# Controller.net
KiCad netlist of a schematic drawn in EAGLE
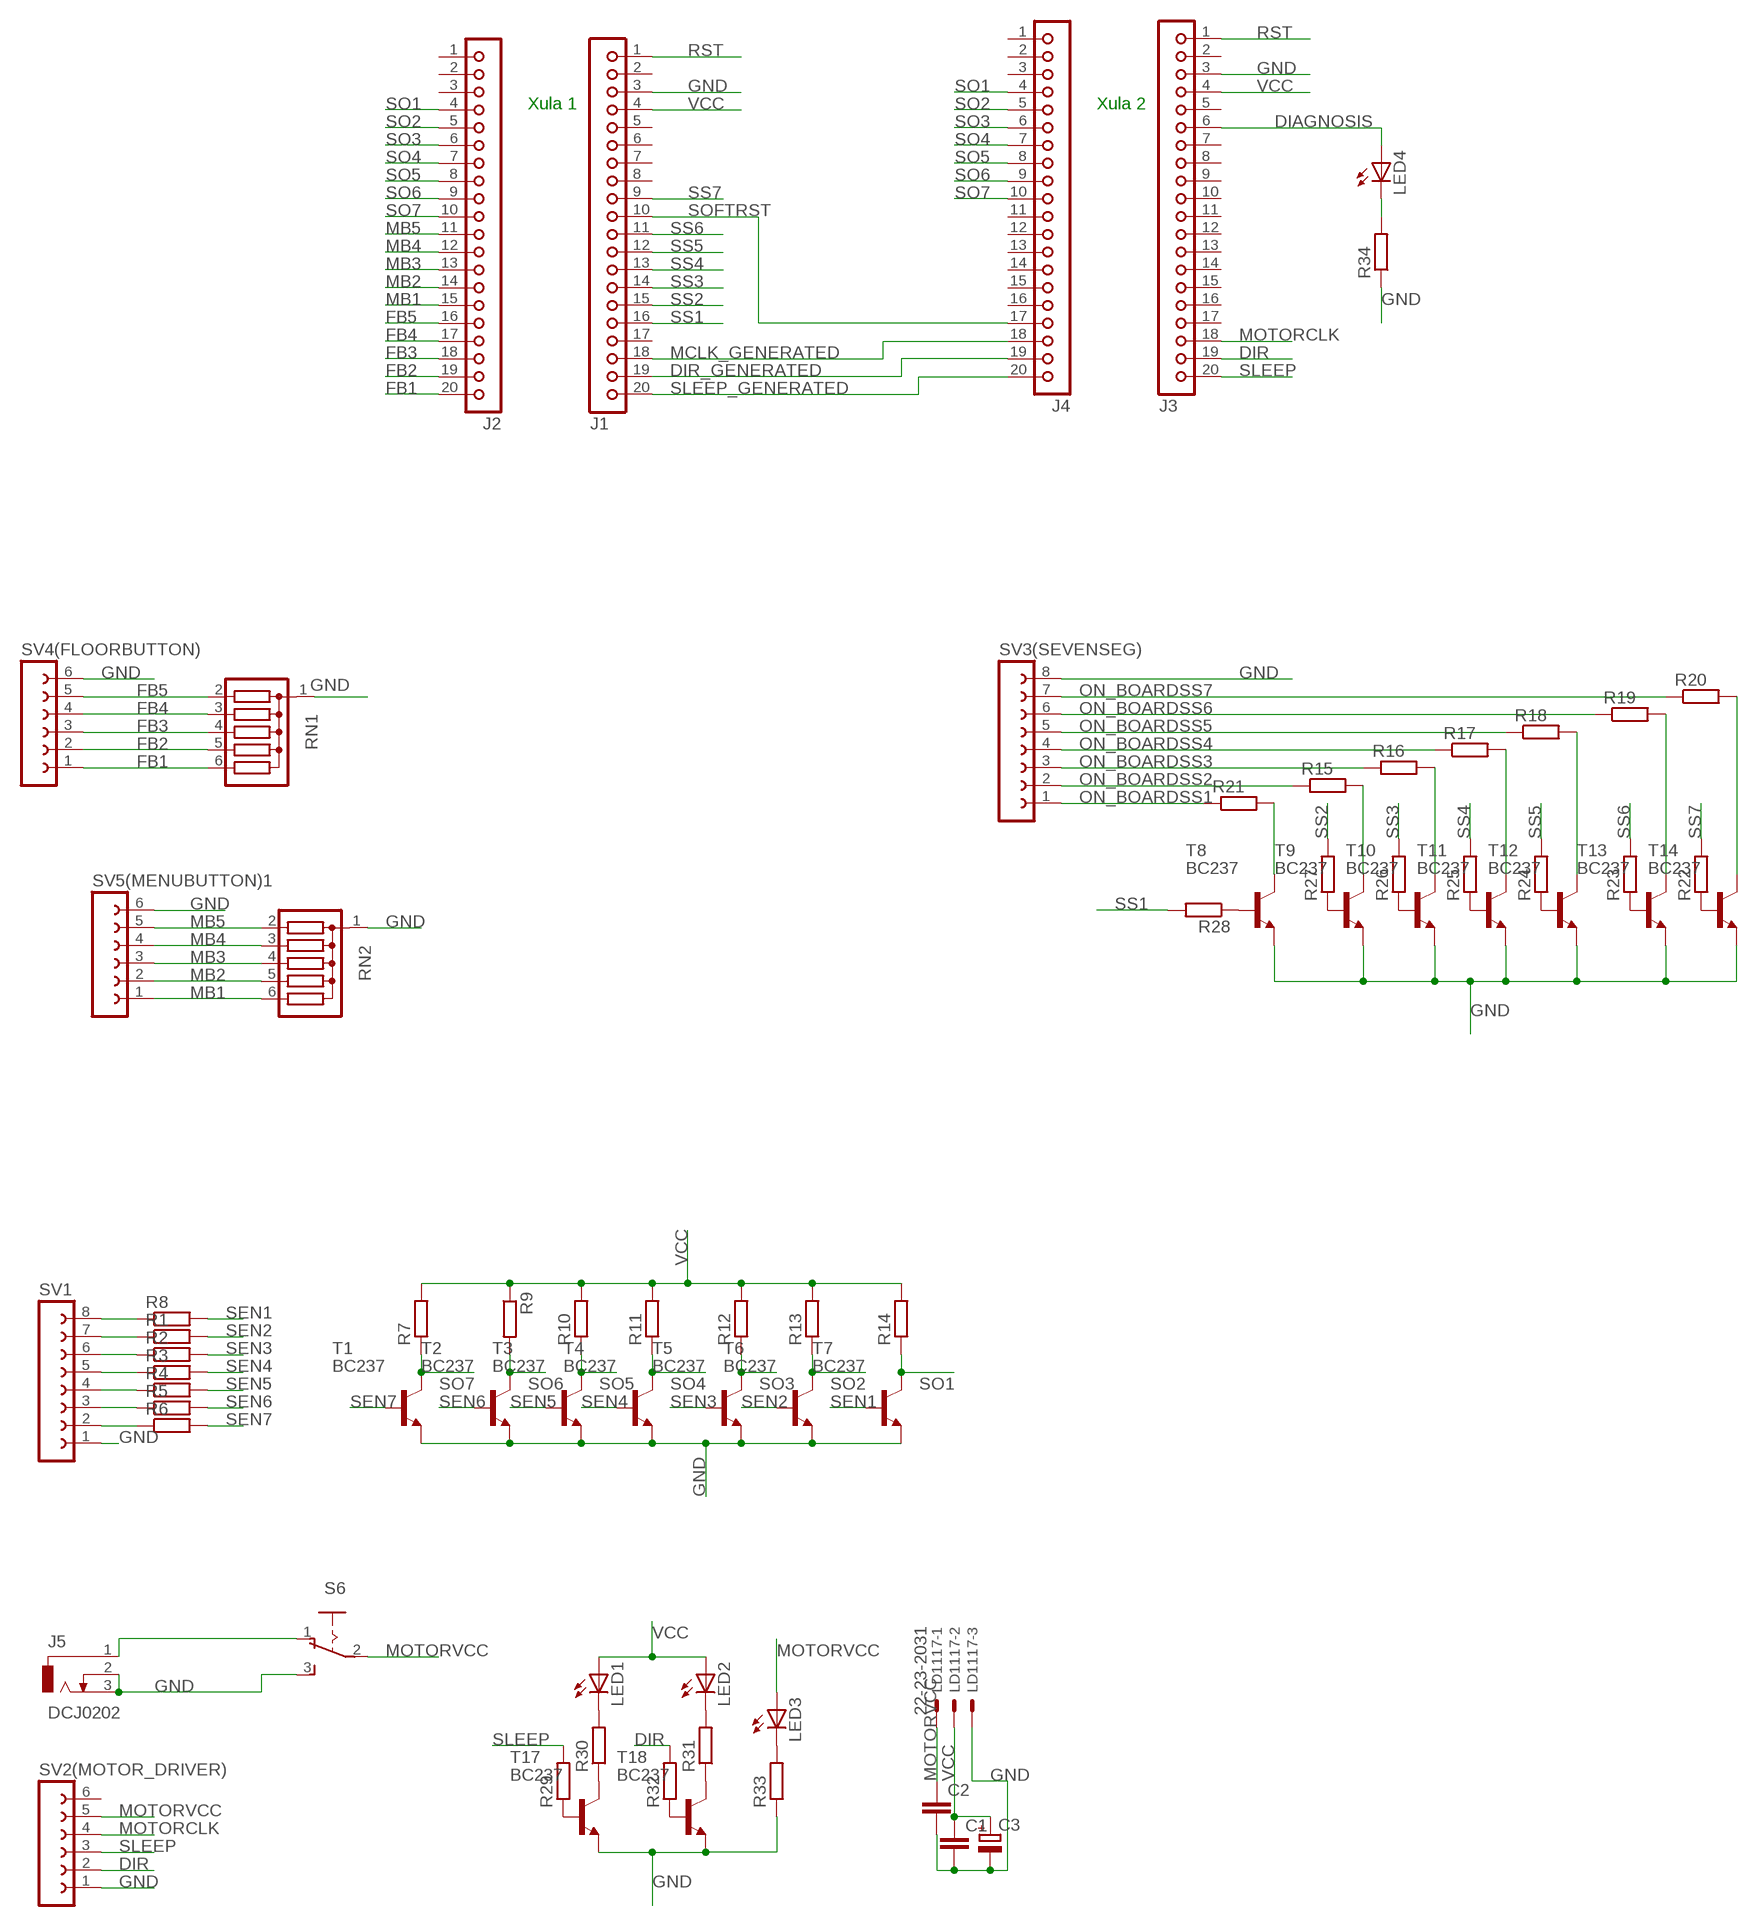
[diagram p0: schematic, sheet 1]

(export (version "E")
  (design (tool "Eeschema 10.0.6"))
  (components
    (comp (ref "C1")
      (value "C-EU025-025X050")
      (footprint "eagle-import:C025-025X050")
      (libsource (lib "eagle-import") (part "C-EU025-025X050"))
    )
    (comp (ref "C2")
      (value "C-EU025-025X050")
      (footprint "eagle-import:C025-025X050")
      (libsource (lib "eagle-import") (part "C-EU025-025X050"))
    )
    (comp (ref "C3")
      (value "CPOL-EUE3.5-8")
      (footprint "eagle-import:E3,5-8")
      (libsource (lib "eagle-import") (part "CPOL-EUE3.5-8"))
    )
    (comp (ref "J1")
      (value "JBK20")
      (footprint "eagle-import:JBK20")
      (libsource (lib "eagle-import") (part "JBK20"))
    )
    (comp (ref "J2")
      (value "JBK20")
      (footprint "eagle-import:JBK20")
      (libsource (lib "eagle-import") (part "JBK20"))
    )
    (comp (ref "J3")
      (value "JBK20")
      (footprint "eagle-import:JBK20")
      (libsource (lib "eagle-import") (part "JBK20"))
    )
    (comp (ref "J4")
      (value "JBK20")
      (footprint "eagle-import:JBK20")
      (libsource (lib "eagle-import") (part "JBK20"))
    )
    (comp (ref "J5")
      (value "DCJ0202")
      (footprint "eagle-import:DCJ0202")
      (libsource (lib "eagle-import") (part "DCJ0202"))
    )
    (comp (ref "LD1117")
      (value "22-23-2031")
      (footprint "eagle-import:22-23-2031")
      (fields (field (name "MF") "MOLEX"))
      (libsource (lib "eagle-import") (part "22-23-2031"))
    )
    (comp (ref "LED1")
      (value "LED3MM")
      (footprint "eagle-import:LED3MM")
      (libsource (lib "eagle-import") (part "LED3MM"))
    )
    (comp (ref "LED2")
      (value "LED3MM")
      (footprint "eagle-import:LED3MM")
      (libsource (lib "eagle-import") (part "LED3MM"))
    )
    (comp (ref "LED3")
      (value "LED3MM")
      (footprint "eagle-import:LED3MM")
      (libsource (lib "eagle-import") (part "LED3MM"))
    )
    (comp (ref "LED4")
      (value "LED3MM")
      (footprint "eagle-import:LED3MM")
      (libsource (lib "eagle-import") (part "LED3MM"))
    )
    (comp (ref "R1")
      (value "R-EU_0204/5")
      (footprint "eagle-import:0204_5")
      (libsource (lib "eagle-import") (part "R-EU_0204/5"))
    )
    (comp (ref "R2")
      (value "R-EU_0204/5")
      (footprint "eagle-import:0204_5")
      (libsource (lib "eagle-import") (part "R-EU_0204/5"))
    )
    (comp (ref "R3")
      (value "R-EU_0204/5")
      (footprint "eagle-import:0204_5")
      (libsource (lib "eagle-import") (part "R-EU_0204/5"))
    )
    (comp (ref "R4")
      (value "R-EU_0204/5")
      (footprint "eagle-import:0204_5")
      (libsource (lib "eagle-import") (part "R-EU_0204/5"))
    )
    (comp (ref "R5")
      (value "R-EU_0204/5")
      (footprint "eagle-import:0204_5")
      (libsource (lib "eagle-import") (part "R-EU_0204/5"))
    )
    (comp (ref "R6")
      (value "R-EU_0204/5")
      (footprint "eagle-import:0204_5")
      (libsource (lib "eagle-import") (part "R-EU_0204/5"))
    )
    (comp (ref "R7")
      (value "R-EU_0204/5")
      (footprint "eagle-import:0204_5")
      (libsource (lib "eagle-import") (part "R-EU_0204/5"))
    )
    (comp (ref "R8")
      (value "R-EU_0204/5")
      (footprint "eagle-import:0204_5")
      (libsource (lib "eagle-import") (part "R-EU_0204/5"))
    )
    (comp (ref "R9")
      (value "R-EU_0204/5")
      (footprint "eagle-import:0204_5")
      (libsource (lib "eagle-import") (part "R-EU_0204/5"))
    )
    (comp (ref "R10")
      (value "R-EU_0204/5")
      (footprint "eagle-import:0204_5")
      (libsource (lib "eagle-import") (part "R-EU_0204/5"))
    )
    (comp (ref "R11")
      (value "R-EU_0204/5")
      (footprint "eagle-import:0204_5")
      (libsource (lib "eagle-import") (part "R-EU_0204/5"))
    )
    (comp (ref "R12")
      (value "R-EU_0204/5")
      (footprint "eagle-import:0204_5")
      (libsource (lib "eagle-import") (part "R-EU_0204/5"))
    )
    (comp (ref "R13")
      (value "R-EU_0204/5")
      (footprint "eagle-import:0204_5")
      (libsource (lib "eagle-import") (part "R-EU_0204/5"))
    )
    (comp (ref "R14")
      (value "R-EU_0204/5")
      (footprint "eagle-import:0204_5")
      (libsource (lib "eagle-import") (part "R-EU_0204/5"))
    )
    (comp (ref "R15")
      (value "R-EU_0204/5")
      (footprint "eagle-import:0204_5")
      (libsource (lib "eagle-import") (part "R-EU_0204/5"))
    )
    (comp (ref "R16")
      (value "R-EU_0204/5")
      (footprint "eagle-import:0204_5")
      (libsource (lib "eagle-import") (part "R-EU_0204/5"))
    )
    (comp (ref "R17")
      (value "R-EU_0204/5")
      (footprint "eagle-import:0204_5")
      (libsource (lib "eagle-import") (part "R-EU_0204/5"))
    )
    (comp (ref "R18")
      (value "R-EU_0204/5")
      (footprint "eagle-import:0204_5")
      (libsource (lib "eagle-import") (part "R-EU_0204/5"))
    )
    (comp (ref "R19")
      (value "R-EU_0204/5")
      (footprint "eagle-import:0204_5")
      (libsource (lib "eagle-import") (part "R-EU_0204/5"))
    )
    (comp (ref "R20")
      (value "R-EU_0204/5")
      (footprint "eagle-import:0204_5")
      (libsource (lib "eagle-import") (part "R-EU_0204/5"))
    )
    (comp (ref "R21")
      (value "R-EU_0204/5")
      (footprint "eagle-import:0204_5")
      (libsource (lib "eagle-import") (part "R-EU_0204/5"))
    )
    (comp (ref "R22")
      (value "R-EU_0204/5")
      (footprint "eagle-import:0204_5")
      (libsource (lib "eagle-import") (part "R-EU_0204/5"))
    )
    (comp (ref "R23")
      (value "R-EU_0204/5")
      (footprint "eagle-import:0204_5")
      (libsource (lib "eagle-import") (part "R-EU_0204/5"))
    )
    (comp (ref "R24")
      (value "R-EU_0204/5")
      (footprint "eagle-import:0204_5")
      (libsource (lib "eagle-import") (part "R-EU_0204/5"))
    )
    (comp (ref "R25")
      (value "R-EU_0204/5")
      (footprint "eagle-import:0204_5")
      (libsource (lib "eagle-import") (part "R-EU_0204/5"))
    )
    (comp (ref "R26")
      (value "R-EU_0204/5")
      (footprint "eagle-import:0204_5")
      (libsource (lib "eagle-import") (part "R-EU_0204/5"))
    )
    (comp (ref "R27")
      (value "R-EU_0204/5")
      (footprint "eagle-import:0204_5")
      (libsource (lib "eagle-import") (part "R-EU_0204/5"))
    )
    (comp (ref "R28")
      (value "R-EU_0204/5")
      (footprint "eagle-import:0204_5")
      (libsource (lib "eagle-import") (part "R-EU_0204/5"))
    )
    (comp (ref "R29")
      (value "R-EU_0204/5")
      (footprint "eagle-import:0204_5")
      (libsource (lib "eagle-import") (part "R-EU_0204/5"))
    )
    (comp (ref "R30")
      (value "R-EU_0204/5")
      (footprint "eagle-import:0204_5")
      (libsource (lib "eagle-import") (part "R-EU_0204/5"))
    )
    (comp (ref "R31")
      (value "R-EU_0204/5")
      (footprint "eagle-import:0204_5")
      (libsource (lib "eagle-import") (part "R-EU_0204/5"))
    )
    (comp (ref "R32")
      (value "R-EU_0204/5")
      (footprint "eagle-import:0204_5")
      (libsource (lib "eagle-import") (part "R-EU_0204/5"))
    )
    (comp (ref "R33")
      (value "R-EU_0204/5")
      (footprint "eagle-import:0204_5")
      (libsource (lib "eagle-import") (part "R-EU_0204/5"))
    )
    (comp (ref "R34")
      (value "R-EU_0204/5")
      (footprint "eagle-import:0204_5")
      (libsource (lib "eagle-import") (part "R-EU_0204/5"))
    )
    (comp (ref "RN1")
      (value "G05R")
      (footprint "eagle-import:SIL6")
      (libsource (lib "eagle-import") (part "G05R"))
    )
    (comp (ref "RN2")
      (value "G05R")
      (footprint "eagle-import:SIL6")
      (libsource (lib "eagle-import") (part "G05R"))
    )
    (comp (ref "S6")
      (value "255SB")
      (footprint "eagle-import:255SB")
      (libsource (lib "eagle-import") (part "255SB"))
    )
    (comp (ref "SV1")
      (value "FE08-1")
      (footprint "eagle-import:FE08")
      (libsource (lib "eagle-import") (part "FE08-1"))
    )
    (comp (ref "SV2(MOTOR_DRIVER)")
      (value "FE06-1")
      (footprint "eagle-import:FE06")
      (libsource (lib "eagle-import") (part "FE06-1"))
    )
    (comp (ref "SV3(SEVENSEG)")
      (value "FE08W")
      (footprint "eagle-import:FE08W")
      (libsource (lib "eagle-import") (part "FE08W"))
    )
    (comp (ref "SV4(FLOORBUTTON)")
      (value "FE06-1")
      (footprint "eagle-import:FE06")
      (libsource (lib "eagle-import") (part "FE06-1"))
    )
    (comp (ref "SV5(MENUBUTTON)1")
      (value "FE06-1")
      (footprint "eagle-import:FE06")
      (libsource (lib "eagle-import") (part "FE06-1"))
    )
    (comp (ref "T1")
      (value "BC237")
      (footprint "eagle-import:TO92")
      (libsource (lib "eagle-import") (part "BC237"))
    )
    (comp (ref "T2")
      (value "BC237")
      (footprint "eagle-import:TO92")
      (libsource (lib "eagle-import") (part "BC237"))
    )
    (comp (ref "T3")
      (value "BC237")
      (footprint "eagle-import:TO92")
      (libsource (lib "eagle-import") (part "BC237"))
    )
    (comp (ref "T4")
      (value "BC237")
      (footprint "eagle-import:TO92")
      (libsource (lib "eagle-import") (part "BC237"))
    )
    (comp (ref "T5")
      (value "BC237")
      (footprint "eagle-import:TO92")
      (libsource (lib "eagle-import") (part "BC237"))
    )
    (comp (ref "T6")
      (value "BC237")
      (footprint "eagle-import:TO92")
      (libsource (lib "eagle-import") (part "BC237"))
    )
    (comp (ref "T7")
      (value "BC237")
      (footprint "eagle-import:TO92")
      (libsource (lib "eagle-import") (part "BC237"))
    )
    (comp (ref "T8")
      (value "BC237")
      (footprint "eagle-import:TO92")
      (libsource (lib "eagle-import") (part "BC237"))
    )
    (comp (ref "T9")
      (value "BC237")
      (footprint "eagle-import:TO92")
      (libsource (lib "eagle-import") (part "BC237"))
    )
    (comp (ref "T10")
      (value "BC237")
      (footprint "eagle-import:TO92")
      (libsource (lib "eagle-import") (part "BC237"))
    )
    (comp (ref "T11")
      (value "BC237")
      (footprint "eagle-import:TO92")
      (libsource (lib "eagle-import") (part "BC237"))
    )
    (comp (ref "T12")
      (value "BC237")
      (footprint "eagle-import:TO92")
      (libsource (lib "eagle-import") (part "BC237"))
    )
    (comp (ref "T13")
      (value "BC237")
      (footprint "eagle-import:TO92")
      (libsource (lib "eagle-import") (part "BC237"))
    )
    (comp (ref "T14")
      (value "BC237")
      (footprint "eagle-import:TO92")
      (libsource (lib "eagle-import") (part "BC237"))
    )
    (comp (ref "T17")
      (value "BC237")
      (footprint "eagle-import:TO92")
      (libsource (lib "eagle-import") (part "BC237"))
    )
    (comp (ref "T18")
      (value "BC237")
      (footprint "eagle-import:TO92")
      (libsource (lib "eagle-import") (part "BC237"))
    )
  )
  (nets
    (net (code "1") (name "/DIAGNOSIS") (class "Default")
      (node (ref "J3") (pin "6") (pinfunction "6_6") (pintype "passive"))
      (node (ref "LED4") (pin "A") (pinfunction "A_A") (pintype "passive"))
    )
    (net (code "2") (name "/DIR") (class "Default")
      (node (ref "J3") (pin "19") (pinfunction "19_19") (pintype "passive"))
      (node (ref "R32") (pin "2") (pinfunction "2_2") (pintype "passive"))
      (node (ref "SV2(MOTOR_DRIVER)") (pin "2") (pinfunction "2_2") (pintype "passive"))
    )
    (net (code "3") (name "/DIR_GENERATED") (class "Default")
      (node (ref "J1") (pin "19") (pinfunction "19_19") (pintype "passive"))
      (node (ref "J4") (pin "19") (pinfunction "19_19") (pintype "passive"))
    )
    (net (code "4") (name "/FB1") (class "Default")
      (node (ref "J2") (pin "20") (pinfunction "20_20") (pintype "passive"))
      (node (ref "RN1") (pin "6") (pinfunction "6_6") (pintype "passive"))
      (node (ref "SV4(FLOORBUTTON)") (pin "1") (pinfunction "1_1") (pintype "passive"))
    )
    (net (code "5") (name "/FB2") (class "Default")
      (node (ref "J2") (pin "19") (pinfunction "19_19") (pintype "passive"))
      (node (ref "RN1") (pin "5") (pinfunction "5_5") (pintype "passive"))
      (node (ref "SV4(FLOORBUTTON)") (pin "2") (pinfunction "2_2") (pintype "passive"))
    )
    (net (code "6") (name "/FB3") (class "Default")
      (node (ref "J2") (pin "18") (pinfunction "18_18") (pintype "passive"))
      (node (ref "RN1") (pin "4") (pinfunction "4_4") (pintype "passive"))
      (node (ref "SV4(FLOORBUTTON)") (pin "3") (pinfunction "3_3") (pintype "passive"))
    )
    (net (code "7") (name "/FB4") (class "Default")
      (node (ref "J2") (pin "17") (pinfunction "17_17") (pintype "passive"))
      (node (ref "RN1") (pin "3") (pinfunction "3_3") (pintype "passive"))
      (node (ref "SV4(FLOORBUTTON)") (pin "4") (pinfunction "4_4") (pintype "passive"))
    )
    (net (code "8") (name "/FB5") (class "Default")
      (node (ref "J2") (pin "16") (pinfunction "16_16") (pintype "passive"))
      (node (ref "RN1") (pin "2") (pinfunction "2_2") (pintype "passive"))
      (node (ref "SV4(FLOORBUTTON)") (pin "5") (pinfunction "5_5") (pintype "passive"))
    )
    (net (code "9") (name "/GND") (class "Default")
      (node (ref "C1") (pin "2") (pinfunction "2_2") (pintype "passive"))
      (node (ref "C2") (pin "2") (pinfunction "2_2") (pintype "passive"))
      (node (ref "C3") (pin "-") (pinfunction "-_-") (pintype "passive"))
      (node (ref "J1") (pin "3") (pinfunction "3_3") (pintype "passive"))
      (node (ref "J3") (pin "3") (pinfunction "3_3") (pintype "passive"))
      (node (ref "J5") (pin "2") (pinfunction "2_2") (pintype "passive"))
      (node (ref "J5") (pin "3") (pinfunction "3_3") (pintype "passive"))
      (node (ref "LD1117") (pin "3") (pinfunction "S_3") (pintype "passive"))
      (node (ref "R33") (pin "1") (pinfunction "1_1") (pintype "passive"))
      (node (ref "R34") (pin "1") (pinfunction "1_1") (pintype "passive"))
      (node (ref "RN1") (pin "1") (pinfunction "1_1") (pintype "passive"))
      (node (ref "RN2") (pin "1") (pinfunction "1_1") (pintype "passive"))
      (node (ref "S6") (pin "3") (pinfunction "S_3") (pintype "passive"))
      (node (ref "SV1") (pin "1") (pinfunction "1_1") (pintype "passive"))
      (node (ref "SV2(MOTOR_DRIVER)") (pin "1") (pinfunction "1_1") (pintype "passive"))
      (node (ref "SV3(SEVENSEG)") (pin "8") (pinfunction "8_8") (pintype "passive"))
      (node (ref "SV4(FLOORBUTTON)") (pin "6") (pinfunction "6_6") (pintype "passive"))
      (node (ref "SV5(MENUBUTTON)1") (pin "6") (pinfunction "6_6") (pintype "passive"))
      (node (ref "T1") (pin "1") (pinfunction "E_1") (pintype "passive"))
      (node (ref "T10") (pin "1") (pinfunction "E_1") (pintype "passive"))
      (node (ref "T11") (pin "1") (pinfunction "E_1") (pintype "passive"))
      (node (ref "T12") (pin "1") (pinfunction "E_1") (pintype "passive"))
      (node (ref "T13") (pin "1") (pinfunction "E_1") (pintype "passive"))
      (node (ref "T14") (pin "1") (pinfunction "E_1") (pintype "passive"))
      (node (ref "T17") (pin "1") (pinfunction "E_1") (pintype "passive"))
      (node (ref "T18") (pin "1") (pinfunction "E_1") (pintype "passive"))
      (node (ref "T2") (pin "1") (pinfunction "E_1") (pintype "passive"))
      (node (ref "T3") (pin "1") (pinfunction "E_1") (pintype "passive"))
      (node (ref "T4") (pin "1") (pinfunction "E_1") (pintype "passive"))
      (node (ref "T5") (pin "1") (pinfunction "E_1") (pintype "passive"))
      (node (ref "T6") (pin "1") (pinfunction "E_1") (pintype "passive"))
      (node (ref "T7") (pin "1") (pinfunction "E_1") (pintype "passive"))
      (node (ref "T8") (pin "1") (pinfunction "E_1") (pintype "passive"))
      (node (ref "T9") (pin "1") (pinfunction "E_1") (pintype "passive"))
    )
    (net (code "10") (name "/MB1") (class "Default")
      (node (ref "J2") (pin "15") (pinfunction "15_15") (pintype "passive"))
      (node (ref "RN2") (pin "6") (pinfunction "6_6") (pintype "passive"))
      (node (ref "SV5(MENUBUTTON)1") (pin "1") (pinfunction "1_1") (pintype "passive"))
    )
    (net (code "11") (name "/MB2") (class "Default")
      (node (ref "J2") (pin "14") (pinfunction "14_14") (pintype "passive"))
      (node (ref "RN2") (pin "5") (pinfunction "5_5") (pintype "passive"))
      (node (ref "SV5(MENUBUTTON)1") (pin "2") (pinfunction "2_2") (pintype "passive"))
    )
    (net (code "12") (name "/MB3") (class "Default")
      (node (ref "J2") (pin "13") (pinfunction "13_13") (pintype "passive"))
      (node (ref "RN2") (pin "4") (pinfunction "4_4") (pintype "passive"))
      (node (ref "SV5(MENUBUTTON)1") (pin "3") (pinfunction "3_3") (pintype "passive"))
    )
    (net (code "13") (name "/MB4") (class "Default")
      (node (ref "J2") (pin "12") (pinfunction "12_12") (pintype "passive"))
      (node (ref "RN2") (pin "3") (pinfunction "3_3") (pintype "passive"))
      (node (ref "SV5(MENUBUTTON)1") (pin "4") (pinfunction "4_4") (pintype "passive"))
    )
    (net (code "14") (name "/MB5") (class "Default")
      (node (ref "J2") (pin "11") (pinfunction "11_11") (pintype "passive"))
      (node (ref "RN2") (pin "2") (pinfunction "2_2") (pintype "passive"))
      (node (ref "SV5(MENUBUTTON)1") (pin "5") (pinfunction "5_5") (pintype "passive"))
    )
    (net (code "15") (name "/MCLK_GENERATED") (class "Default")
      (node (ref "J1") (pin "18") (pinfunction "18_18") (pintype "passive"))
      (node (ref "J4") (pin "18") (pinfunction "18_18") (pintype "passive"))
    )
    (net (code "16") (name "/MOTORCLK") (class "Default")
      (node (ref "J3") (pin "18") (pinfunction "18_18") (pintype "passive"))
      (node (ref "SV2(MOTOR_DRIVER)") (pin "4") (pinfunction "4_4") (pintype "passive"))
    )
    (net (code "17") (name "/MOTORVCC") (class "Default")
      (node (ref "C2") (pin "1") (pinfunction "1_1") (pintype "passive"))
      (node (ref "LD1117") (pin "1") (pinfunction "S_1") (pintype "passive"))
      (node (ref "LED3") (pin "A") (pinfunction "A_A") (pintype "passive"))
      (node (ref "S6") (pin "2") (pinfunction "P_2") (pintype "passive"))
      (node (ref "SV2(MOTOR_DRIVER)") (pin "5") (pinfunction "5_5") (pintype "passive"))
    )
    (net (code "18") (name "/ON_BOARDSS1") (class "Default")
      (node (ref "R21") (pin "1") (pinfunction "1_1") (pintype "passive"))
      (node (ref "SV3(SEVENSEG)") (pin "1") (pinfunction "1_1") (pintype "passive"))
    )
    (net (code "19") (name "/ON_BOARDSS2") (class "Default")
      (node (ref "R15") (pin "1") (pinfunction "1_1") (pintype "passive"))
      (node (ref "SV3(SEVENSEG)") (pin "2") (pinfunction "2_2") (pintype "passive"))
    )
    (net (code "20") (name "/ON_BOARDSS3") (class "Default")
      (node (ref "R16") (pin "1") (pinfunction "1_1") (pintype "passive"))
      (node (ref "SV3(SEVENSEG)") (pin "3") (pinfunction "3_3") (pintype "passive"))
    )
    (net (code "21") (name "/ON_BOARDSS4") (class "Default")
      (node (ref "R17") (pin "1") (pinfunction "1_1") (pintype "passive"))
      (node (ref "SV3(SEVENSEG)") (pin "4") (pinfunction "4_4") (pintype "passive"))
    )
    (net (code "22") (name "/ON_BOARDSS5") (class "Default")
      (node (ref "R18") (pin "1") (pinfunction "1_1") (pintype "passive"))
      (node (ref "SV3(SEVENSEG)") (pin "5") (pinfunction "5_5") (pintype "passive"))
    )
    (net (code "23") (name "/ON_BOARDSS6") (class "Default")
      (node (ref "R19") (pin "1") (pinfunction "1_1") (pintype "passive"))
      (node (ref "SV3(SEVENSEG)") (pin "6") (pinfunction "6_6") (pintype "passive"))
    )
    (net (code "24") (name "/ON_BOARDSS7") (class "Default")
      (node (ref "R20") (pin "1") (pinfunction "1_1") (pintype "passive"))
      (node (ref "SV3(SEVENSEG)") (pin "7") (pinfunction "7_7") (pintype "passive"))
    )
    (net (code "25") (name "/RST") (class "Default")
      (node (ref "J1") (pin "1") (pinfunction "1_1") (pintype "passive"))
      (node (ref "J3") (pin "1") (pinfunction "1_1") (pintype "passive"))
    )
    (net (code "26") (name "/SEN1") (class "Default")
      (node (ref "R8") (pin "2") (pinfunction "2_2") (pintype "passive"))
      (node (ref "T7") (pin "2") (pinfunction "B_2") (pintype "passive"))
    )
    (net (code "27") (name "/SEN2") (class "Default")
      (node (ref "R1") (pin "2") (pinfunction "2_2") (pintype "passive"))
      (node (ref "T6") (pin "2") (pinfunction "B_2") (pintype "passive"))
    )
    (net (code "28") (name "/SEN3") (class "Default")
      (node (ref "R2") (pin "2") (pinfunction "2_2") (pintype "passive"))
      (node (ref "T5") (pin "2") (pinfunction "B_2") (pintype "passive"))
    )
    (net (code "29") (name "/SEN4") (class "Default")
      (node (ref "R3") (pin "2") (pinfunction "2_2") (pintype "passive"))
      (node (ref "T4") (pin "2") (pinfunction "B_2") (pintype "passive"))
    )
    (net (code "30") (name "/SEN5") (class "Default")
      (node (ref "R4") (pin "2") (pinfunction "2_2") (pintype "passive"))
      (node (ref "T3") (pin "2") (pinfunction "B_2") (pintype "passive"))
    )
    (net (code "31") (name "/SEN6") (class "Default")
      (node (ref "R5") (pin "2") (pinfunction "2_2") (pintype "passive"))
      (node (ref "T2") (pin "2") (pinfunction "B_2") (pintype "passive"))
    )
    (net (code "32") (name "/SEN7") (class "Default")
      (node (ref "R6") (pin "2") (pinfunction "2_2") (pintype "passive"))
      (node (ref "T1") (pin "2") (pinfunction "B_2") (pintype "passive"))
    )
    (net (code "33") (name "/SLEEP") (class "Default")
      (node (ref "J3") (pin "20") (pinfunction "20_20") (pintype "passive"))
      (node (ref "R29") (pin "2") (pinfunction "2_2") (pintype "passive"))
      (node (ref "SV2(MOTOR_DRIVER)") (pin "3") (pinfunction "3_3") (pintype "passive"))
    )
    (net (code "34") (name "/SLEEP_GENERATED") (class "Default")
      (node (ref "J1") (pin "20") (pinfunction "20_20") (pintype "passive"))
      (node (ref "J4") (pin "20") (pinfunction "20_20") (pintype "passive"))
    )
    (net (code "35") (name "/SO1") (class "Default")
      (node (ref "J2") (pin "4") (pinfunction "4_4") (pintype "passive"))
      (node (ref "J4") (pin "4") (pinfunction "4_4") (pintype "passive"))
      (node (ref "R14") (pin "1") (pinfunction "1_1") (pintype "passive"))
      (node (ref "T7") (pin "3") (pinfunction "C_3") (pintype "passive"))
    )
    (net (code "36") (name "/SO2") (class "Default")
      (node (ref "J2") (pin "5") (pinfunction "5_5") (pintype "passive"))
      (node (ref "J4") (pin "5") (pinfunction "5_5") (pintype "passive"))
      (node (ref "R13") (pin "1") (pinfunction "1_1") (pintype "passive"))
      (node (ref "T6") (pin "3") (pinfunction "C_3") (pintype "passive"))
    )
    (net (code "37") (name "/SO3") (class "Default")
      (node (ref "J2") (pin "6") (pinfunction "6_6") (pintype "passive"))
      (node (ref "J4") (pin "6") (pinfunction "6_6") (pintype "passive"))
      (node (ref "R12") (pin "1") (pinfunction "1_1") (pintype "passive"))
      (node (ref "T5") (pin "3") (pinfunction "C_3") (pintype "passive"))
    )
    (net (code "38") (name "/SO4") (class "Default")
      (node (ref "J2") (pin "7") (pinfunction "7_7") (pintype "passive"))
      (node (ref "J4") (pin "7") (pinfunction "7_7") (pintype "passive"))
      (node (ref "R11") (pin "1") (pinfunction "1_1") (pintype "passive"))
      (node (ref "T4") (pin "3") (pinfunction "C_3") (pintype "passive"))
    )
    (net (code "39") (name "/SO5") (class "Default")
      (node (ref "J2") (pin "8") (pinfunction "8_8") (pintype "passive"))
      (node (ref "J4") (pin "8") (pinfunction "8_8") (pintype "passive"))
      (node (ref "R10") (pin "1") (pinfunction "1_1") (pintype "passive"))
      (node (ref "T3") (pin "3") (pinfunction "C_3") (pintype "passive"))
    )
    (net (code "40") (name "/SO6") (class "Default")
      (node (ref "J2") (pin "9") (pinfunction "9_9") (pintype "passive"))
      (node (ref "J4") (pin "9") (pinfunction "9_9") (pintype "passive"))
      (node (ref "R9") (pin "2") (pinfunction "2_2") (pintype "passive"))
      (node (ref "T2") (pin "3") (pinfunction "C_3") (pintype "passive"))
    )
    (net (code "41") (name "/SO7") (class "Default")
      (node (ref "J2") (pin "10") (pinfunction "10_10") (pintype "passive"))
      (node (ref "J4") (pin "10") (pinfunction "10_10") (pintype "passive"))
      (node (ref "R7") (pin "1") (pinfunction "1_1") (pintype "passive"))
      (node (ref "T1") (pin "3") (pinfunction "C_3") (pintype "passive"))
    )
    (net (code "42") (name "/SOFTRST") (class "Default")
      (node (ref "J1") (pin "10") (pinfunction "10_10") (pintype "passive"))
      (node (ref "J4") (pin "17") (pinfunction "17_17") (pintype "passive"))
    )
    (net (code "43") (name "/SS1") (class "Default")
      (node (ref "J1") (pin "16") (pinfunction "16_16") (pintype "passive"))
      (node (ref "R28") (pin "2") (pinfunction "2_2") (pintype "passive"))
    )
    (net (code "44") (name "/SS2") (class "Default")
      (node (ref "J1") (pin "15") (pinfunction "15_15") (pintype "passive"))
      (node (ref "R27") (pin "2") (pinfunction "2_2") (pintype "passive"))
    )
    (net (code "45") (name "/SS3") (class "Default")
      (node (ref "J1") (pin "14") (pinfunction "14_14") (pintype "passive"))
      (node (ref "R26") (pin "2") (pinfunction "2_2") (pintype "passive"))
    )
    (net (code "46") (name "/SS4") (class "Default")
      (node (ref "J1") (pin "13") (pinfunction "13_13") (pintype "passive"))
      (node (ref "R25") (pin "2") (pinfunction "2_2") (pintype "passive"))
    )
    (net (code "47") (name "/SS5") (class "Default")
      (node (ref "J1") (pin "12") (pinfunction "12_12") (pintype "passive"))
      (node (ref "R24") (pin "2") (pinfunction "2_2") (pintype "passive"))
    )
    (net (code "48") (name "/SS6") (class "Default")
      (node (ref "J1") (pin "11") (pinfunction "11_11") (pintype "passive"))
      (node (ref "R23") (pin "2") (pinfunction "2_2") (pintype "passive"))
    )
    (net (code "49") (name "/SS7") (class "Default")
      (node (ref "J1") (pin "9") (pinfunction "9_9") (pintype "passive"))
      (node (ref "R22") (pin "2") (pinfunction "2_2") (pintype "passive"))
    )
    (net (code "50") (name "/VCC") (class "Default")
      (node (ref "C1") (pin "1") (pinfunction "1_1") (pintype "passive"))
      (node (ref "C3") (pin "+") (pinfunction "+_+") (pintype "passive"))
      (node (ref "J1") (pin "4") (pinfunction "4_4") (pintype "passive"))
      (node (ref "J3") (pin "4") (pinfunction "4_4") (pintype "passive"))
      (node (ref "LD1117") (pin "2") (pinfunction "S_2") (pintype "passive"))
      (node (ref "LED1") (pin "A") (pinfunction "A_A") (pintype "passive"))
      (node (ref "LED2") (pin "A") (pinfunction "A_A") (pintype "passive"))
      (node (ref "R10") (pin "2") (pinfunction "2_2") (pintype "passive"))
      (node (ref "R11") (pin "2") (pinfunction "2_2") (pintype "passive"))
      (node (ref "R12") (pin "2") (pinfunction "2_2") (pintype "passive"))
      (node (ref "R13") (pin "2") (pinfunction "2_2") (pintype "passive"))
      (node (ref "R14") (pin "2") (pinfunction "2_2") (pintype "passive"))
      (node (ref "R7") (pin "2") (pinfunction "2_2") (pintype "passive"))
      (node (ref "R9") (pin "1") (pinfunction "1_1") (pintype "passive"))
    )
    (net (code "51") (name "Net-(LED1-C)") (class "Default")
      (node (ref "LED1") (pin "K") (pinfunction "C_K") (pintype "passive"))
      (node (ref "R30") (pin "2") (pinfunction "2_2") (pintype "passive"))
    )
    (net (code "52") (name "Net-(LED2-C)") (class "Default")
      (node (ref "LED2") (pin "K") (pinfunction "C_K") (pintype "passive"))
      (node (ref "R31") (pin "2") (pinfunction "2_2") (pintype "passive"))
    )
    (net (code "53") (name "Net-(LED3-C)") (class "Default")
      (node (ref "LED3") (pin "K") (pinfunction "C_K") (pintype "passive"))
      (node (ref "R33") (pin "2") (pinfunction "2_2") (pintype "passive"))
    )
    (net (code "54") (name "Net-(LED4-C)") (class "Default")
      (node (ref "LED4") (pin "K") (pinfunction "C_K") (pintype "passive"))
      (node (ref "R34") (pin "2") (pinfunction "2_2") (pintype "passive"))
    )
    (net (code "55") (name "Net-(R1-Pad1)") (class "Default")
      (node (ref "R1") (pin "1") (pinfunction "1_1") (pintype "passive"))
      (node (ref "SV1") (pin "7") (pinfunction "7_7") (pintype "passive"))
    )
    (net (code "56") (name "Net-(R2-Pad1)") (class "Default")
      (node (ref "R2") (pin "1") (pinfunction "1_1") (pintype "passive"))
      (node (ref "SV1") (pin "6") (pinfunction "6_6") (pintype "passive"))
    )
    (net (code "57") (name "Net-(R3-Pad1)") (class "Default")
      (node (ref "R3") (pin "1") (pinfunction "1_1") (pintype "passive"))
      (node (ref "SV1") (pin "5") (pinfunction "5_5") (pintype "passive"))
    )
    (net (code "58") (name "Net-(R4-Pad1)") (class "Default")
      (node (ref "R4") (pin "1") (pinfunction "1_1") (pintype "passive"))
      (node (ref "SV1") (pin "4") (pinfunction "4_4") (pintype "passive"))
    )
    (net (code "59") (name "Net-(R5-Pad1)") (class "Default")
      (node (ref "R5") (pin "1") (pinfunction "1_1") (pintype "passive"))
      (node (ref "SV1") (pin "3") (pinfunction "3_3") (pintype "passive"))
    )
    (net (code "60") (name "Net-(R6-Pad1)") (class "Default")
      (node (ref "R6") (pin "1") (pinfunction "1_1") (pintype "passive"))
      (node (ref "SV1") (pin "2") (pinfunction "2_2") (pintype "passive"))
    )
    (net (code "61") (name "Net-(R8-Pad1)") (class "Default")
      (node (ref "R8") (pin "1") (pinfunction "1_1") (pintype "passive"))
      (node (ref "SV1") (pin "8") (pinfunction "8_8") (pintype "passive"))
    )
    (net (code "62") (name "Net-(S6-O)") (class "Default")
      (node (ref "J5") (pin "1") (pinfunction "1_1") (pintype "passive"))
      (node (ref "S6") (pin "1") (pinfunction "O_1") (pintype "passive"))
    )
    (net (code "63") (name "Net-(T8-B)") (class "Default")
      (node (ref "R28") (pin "1") (pinfunction "1_1") (pintype "passive"))
      (node (ref "T8") (pin "2") (pinfunction "B_2") (pintype "passive"))
    )
    (net (code "64") (name "Net-(T8-C)") (class "Default")
      (node (ref "R21") (pin "2") (pinfunction "2_2") (pintype "passive"))
      (node (ref "T8") (pin "3") (pinfunction "C_3") (pintype "passive"))
    )
    (net (code "65") (name "Net-(T9-B)") (class "Default")
      (node (ref "R27") (pin "1") (pinfunction "1_1") (pintype "passive"))
      (node (ref "T9") (pin "2") (pinfunction "B_2") (pintype "passive"))
    )
    (net (code "66") (name "Net-(T9-C)") (class "Default")
      (node (ref "R15") (pin "2") (pinfunction "2_2") (pintype "passive"))
      (node (ref "T9") (pin "3") (pinfunction "C_3") (pintype "passive"))
    )
    (net (code "67") (name "Net-(T10-B)") (class "Default")
      (node (ref "R26") (pin "1") (pinfunction "1_1") (pintype "passive"))
      (node (ref "T10") (pin "2") (pinfunction "B_2") (pintype "passive"))
    )
    (net (code "68") (name "Net-(T10-C)") (class "Default")
      (node (ref "R16") (pin "2") (pinfunction "2_2") (pintype "passive"))
      (node (ref "T10") (pin "3") (pinfunction "C_3") (pintype "passive"))
    )
    (net (code "69") (name "Net-(T11-B)") (class "Default")
      (node (ref "R25") (pin "1") (pinfunction "1_1") (pintype "passive"))
      (node (ref "T11") (pin "2") (pinfunction "B_2") (pintype "passive"))
    )
    (net (code "70") (name "Net-(T11-C)") (class "Default")
      (node (ref "R17") (pin "2") (pinfunction "2_2") (pintype "passive"))
      (node (ref "T11") (pin "3") (pinfunction "C_3") (pintype "passive"))
    )
    (net (code "71") (name "Net-(T12-B)") (class "Default")
      (node (ref "R24") (pin "1") (pinfunction "1_1") (pintype "passive"))
      (node (ref "T12") (pin "2") (pinfunction "B_2") (pintype "passive"))
    )
    (net (code "72") (name "Net-(T12-C)") (class "Default")
      (node (ref "R18") (pin "2") (pinfunction "2_2") (pintype "passive"))
      (node (ref "T12") (pin "3") (pinfunction "C_3") (pintype "passive"))
    )
    (net (code "73") (name "Net-(T13-B)") (class "Default")
      (node (ref "R23") (pin "1") (pinfunction "1_1") (pintype "passive"))
      (node (ref "T13") (pin "2") (pinfunction "B_2") (pintype "passive"))
    )
    (net (code "74") (name "Net-(T13-C)") (class "Default")
      (node (ref "R19") (pin "2") (pinfunction "2_2") (pintype "passive"))
      (node (ref "T13") (pin "3") (pinfunction "C_3") (pintype "passive"))
    )
    (net (code "75") (name "Net-(T14-B)") (class "Default")
      (node (ref "R22") (pin "1") (pinfunction "1_1") (pintype "passive"))
      (node (ref "T14") (pin "2") (pinfunction "B_2") (pintype "passive"))
    )
    (net (code "76") (name "Net-(T14-C)") (class "Default")
      (node (ref "R20") (pin "2") (pinfunction "2_2") (pintype "passive"))
      (node (ref "T14") (pin "3") (pinfunction "C_3") (pintype "passive"))
    )
    (net (code "77") (name "Net-(T17-B)") (class "Default")
      (node (ref "R29") (pin "1") (pinfunction "1_1") (pintype "passive"))
      (node (ref "T17") (pin "2") (pinfunction "B_2") (pintype "passive"))
    )
    (net (code "78") (name "Net-(T17-C)") (class "Default")
      (node (ref "R30") (pin "1") (pinfunction "1_1") (pintype "passive"))
      (node (ref "T17") (pin "3") (pinfunction "C_3") (pintype "passive"))
    )
    (net (code "79") (name "Net-(T18-B)") (class "Default")
      (node (ref "R32") (pin "1") (pinfunction "1_1") (pintype "passive"))
      (node (ref "T18") (pin "2") (pinfunction "B_2") (pintype "passive"))
    )
    (net (code "80") (name "Net-(T18-C)") (class "Default")
      (node (ref "R31") (pin "1") (pinfunction "1_1") (pintype "passive"))
      (node (ref "T18") (pin "3") (pinfunction "C_3") (pintype "passive"))
    )
    (net (code "81") (name "unconnected-(J1-Pad2)") (class "Default")
      (node (ref "J1") (pin "2") (pinfunction "2_2") (pintype "passive"))
    )
    (net (code "82") (name "unconnected-(J1-Pad5)") (class "Default")
      (node (ref "J1") (pin "5") (pinfunction "5_5") (pintype "passive"))
    )
    (net (code "83") (name "unconnected-(J1-Pad6)") (class "Default")
      (node (ref "J1") (pin "6") (pinfunction "6_6") (pintype "passive"))
    )
    (net (code "84") (name "unconnected-(J1-Pad7)") (class "Default")
      (node (ref "J1") (pin "7") (pinfunction "7_7") (pintype "passive"))
    )
    (net (code "85") (name "unconnected-(J1-Pad8)") (class "Default")
      (node (ref "J1") (pin "8") (pinfunction "8_8") (pintype "passive"))
    )
    (net (code "86") (name "unconnected-(J1-Pad17)") (class "Default")
      (node (ref "J1") (pin "17") (pinfunction "17_17") (pintype "passive"))
    )
    (net (code "87") (name "unconnected-(J2-Pad1)") (class "Default")
      (node (ref "J2") (pin "1") (pinfunction "1_1") (pintype "passive"))
    )
    (net (code "88") (name "unconnected-(J2-Pad2)") (class "Default")
      (node (ref "J2") (pin "2") (pinfunction "2_2") (pintype "passive"))
    )
    (net (code "89") (name "unconnected-(J2-Pad3)") (class "Default")
      (node (ref "J2") (pin "3") (pinfunction "3_3") (pintype "passive"))
    )
    (net (code "90") (name "unconnected-(J3-Pad2)") (class "Default")
      (node (ref "J3") (pin "2") (pinfunction "2_2") (pintype "passive"))
    )
    (net (code "91") (name "unconnected-(J3-Pad5)") (class "Default")
      (node (ref "J3") (pin "5") (pinfunction "5_5") (pintype "passive"))
    )
    (net (code "92") (name "unconnected-(J3-Pad7)") (class "Default")
      (node (ref "J3") (pin "7") (pinfunction "7_7") (pintype "passive"))
    )
    (net (code "93") (name "unconnected-(J3-Pad8)") (class "Default")
      (node (ref "J3") (pin "8") (pinfunction "8_8") (pintype "passive"))
    )
    (net (code "94") (name "unconnected-(J3-Pad9)") (class "Default")
      (node (ref "J3") (pin "9") (pinfunction "9_9") (pintype "passive"))
    )
    (net (code "95") (name "unconnected-(J3-Pad10)") (class "Default")
      (node (ref "J3") (pin "10") (pinfunction "10_10") (pintype "passive"))
    )
    (net (code "96") (name "unconnected-(J3-Pad11)") (class "Default")
      (node (ref "J3") (pin "11") (pinfunction "11_11") (pintype "passive"))
    )
    (net (code "97") (name "unconnected-(J3-Pad12)") (class "Default")
      (node (ref "J3") (pin "12") (pinfunction "12_12") (pintype "passive"))
    )
    (net (code "98") (name "unconnected-(J3-Pad13)") (class "Default")
      (node (ref "J3") (pin "13") (pinfunction "13_13") (pintype "passive"))
    )
    (net (code "99") (name "unconnected-(J3-Pad14)") (class "Default")
      (node (ref "J3") (pin "14") (pinfunction "14_14") (pintype "passive"))
    )
    (net (code "100") (name "unconnected-(J3-Pad15)") (class "Default")
      (node (ref "J3") (pin "15") (pinfunction "15_15") (pintype "passive"))
    )
    (net (code "101") (name "unconnected-(J3-Pad16)") (class "Default")
      (node (ref "J3") (pin "16") (pinfunction "16_16") (pintype "passive"))
    )
    (net (code "102") (name "unconnected-(J3-Pad17)") (class "Default")
      (node (ref "J3") (pin "17") (pinfunction "17_17") (pintype "passive"))
    )
    (net (code "103") (name "unconnected-(J4-Pad1)") (class "Default")
      (node (ref "J4") (pin "1") (pinfunction "1_1") (pintype "passive"))
    )
    (net (code "104") (name "unconnected-(J4-Pad2)") (class "Default")
      (node (ref "J4") (pin "2") (pinfunction "2_2") (pintype "passive"))
    )
    (net (code "105") (name "unconnected-(J4-Pad3)") (class "Default")
      (node (ref "J4") (pin "3") (pinfunction "3_3") (pintype "passive"))
    )
    (net (code "106") (name "unconnected-(J4-Pad11)") (class "Default")
      (node (ref "J4") (pin "11") (pinfunction "11_11") (pintype "passive"))
    )
    (net (code "107") (name "unconnected-(J4-Pad12)") (class "Default")
      (node (ref "J4") (pin "12") (pinfunction "12_12") (pintype "passive"))
    )
    (net (code "108") (name "unconnected-(J4-Pad13)") (class "Default")
      (node (ref "J4") (pin "13") (pinfunction "13_13") (pintype "passive"))
    )
    (net (code "109") (name "unconnected-(J4-Pad14)") (class "Default")
      (node (ref "J4") (pin "14") (pinfunction "14_14") (pintype "passive"))
    )
    (net (code "110") (name "unconnected-(J4-Pad15)") (class "Default")
      (node (ref "J4") (pin "15") (pinfunction "15_15") (pintype "passive"))
    )
    (net (code "111") (name "unconnected-(J4-Pad16)") (class "Default")
      (node (ref "J4") (pin "16") (pinfunction "16_16") (pintype "passive"))
    )
    (net (code "112") (name "unconnected-(SV2(MOTOR_DRIVER)-Pad6)") (class "Default")
      (node (ref "SV2(MOTOR_DRIVER)") (pin "6") (pinfunction "6_6") (pintype "passive"))
    )
  )
)
